# Power.net
KiCad netlist of a schematic drawn in Altium Designer
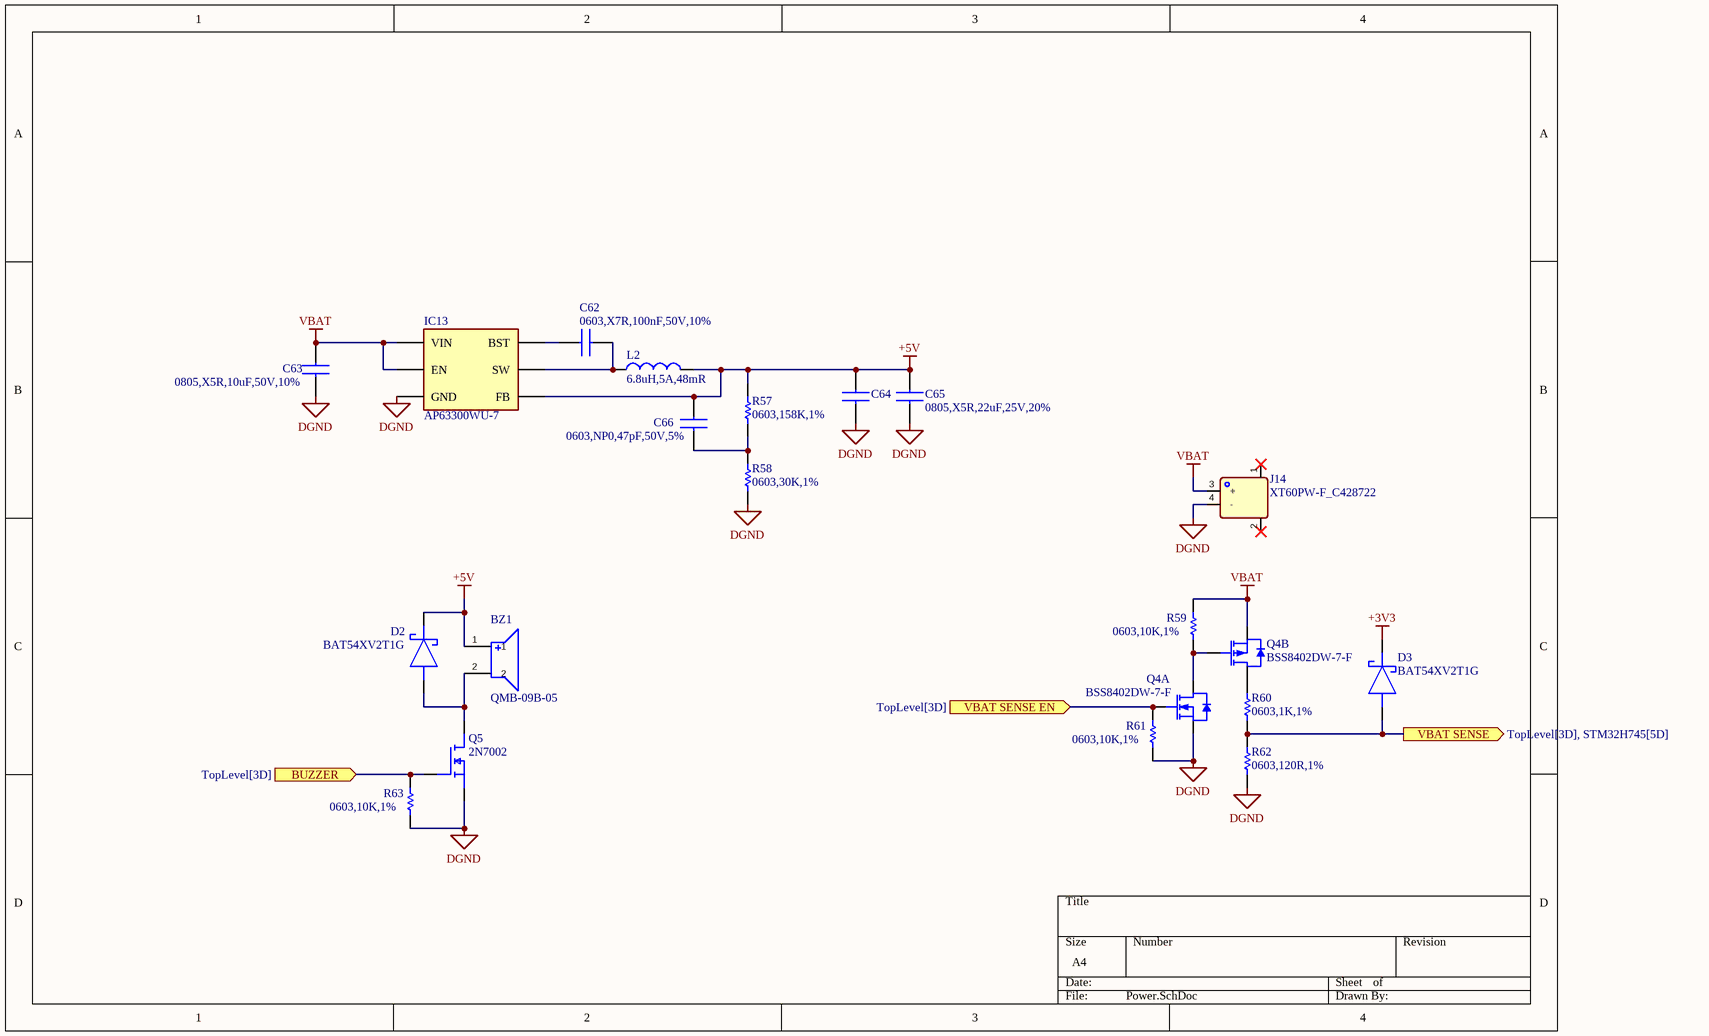
[diagram p0: Power.SchDoc]

(export (version "E")
  (design (tool "Eeschema 10.0.6"))
  (components
    (comp (ref "BZ1")
      (value "QMB-09B-05")
      (footprint "QMB-09B-05")
      (fields (field (name "LCSC PART #") "C161819"))
      (libsource (lib "flight-controller") (part "QMB-09B-05"))
    )
    (comp (ref "C62")
      (value "0603,X7R,100nF,50V,10%")
      (footprint "CAPC1608X90N")
      (description "50V 100nF X7R ±10% 0603 Multilayer Ceramic Capacitors MLCC - SMD/SMT ROHS")
      (fields (field (name "LCSC PART #") "C14663") (field (name "MANU PART #") "CC0603KRX7R9BB104"))
      (libsource (lib "flight-controller") (part "CC0603KRX7R9BB104"))
    )
    (comp (ref "C63")
      (value "0805,X5R,10uF,50V,10%")
      (footprint "CAPC2012X145N")
      (description "10uF 50V X5R ±10% 0805 Multilayer Ceramic Capacitors MLCC - SMD/SMT ROHS")
      (fields (field (name "LCSC PART #") "C440198") (field (name "MANU PART #") "GRM21BR61H106KE43L"))
      (libsource (lib "flight-controller") (part "GRM21BR61H106KE43L"))
    )
    (comp (ref "C64")
      (value "0805,X5R,22uF,25V,20%")
      (footprint "CAPC2012X145N")
      (description "22uF ±20% 25V Ceramic Capacitor X5R 0805")
      (fields (field (name "LCSC PART #") "C45783") (field (name "MANU PART #") "CL21A226MAQNNNE"))
      (libsource (lib "flight-controller") (part "CL21A226MAQNNNE"))
    )
    (comp (ref "C65")
      (value "0805,X5R,22uF,25V,20%")
      (footprint "CAPC2012X145N")
      (description "22uF ±20% 25V Ceramic Capacitor X5R 0805")
      (fields (field (name "LCSC PART #") "C45783") (field (name "MANU PART #") "CL21A226MAQNNNE"))
      (libsource (lib "flight-controller") (part "CL21A226MAQNNNE"))
    )
    (comp (ref "C66")
      (value "0603,NP0,47pF,50V,5%")
      (footprint "CAPC1608X90N")
      (description "47 pF ±5% 50V Ceramic Capacitor C0G, NP0 0603 (1608 Metric)")
      (fields (field (name "MANU PART #") "CL10C470JB8NNNC") (field (name "LCSC PART #") "C1671"))
      (libsource (lib "flight-controller") (part "CL10C470JB8NNNC"))
    )
    (comp (ref "D2")
      (value "BAT54XV2T1G")
      (footprint "SOD523")
      (description "Diode 30V 200mA Surface Mount SOD-523")
      (fields (field (name "LCSC PART #") "C81572"))
      (libsource (lib "flight-controller") (part "BAT54XV2T1G"))
    )
    (comp (ref "D3")
      (value "BAT54XV2T1G")
      (footprint "SOD523")
      (description "Diode 30V 200mA Surface Mount SOD-523")
      (fields (field (name "LCSC PART #") "C81572"))
      (libsource (lib "flight-controller") (part "BAT54XV2T1G"))
    )
    (comp (ref "IC13")
      (value "AP63300WU-7")
      (footprint "SOT95P280X90-6N")
      (description "3.8V to 32V Input, 3A Low IQ Synchronous Buck Converter with Enhanced EMI Reduction")
      (fields (field (name "LCSC PART #") "C2158012"))
      (libsource (lib "flight-controller") (part "AP63300WU-7"))
    )
    (comp (ref "J14")
      (value "XT60PW-F_C428722")
      (footprint "XT60PW-F_C428722")
      (description "Horizontal plug Yellow - Power connector / plug connector")
      (fields (field (name "LCSC PART #") "C428722") (field (name "MANU PART #") "XT60PW-F"))
      (libsource (lib "flight-controller") (part "XT60PW-F_C428722"))
    )
    (comp (ref "L2")
      (value "6.8uH,5A,48mR")
      (footprint "FXL0630-6R8-M")
      (description "48mΩ 5A 6.8uH 6A Molded Inductor ±20% SMD,7x6.6mm Power Inductors ROHS")
      (fields (field (name "MANU PART #") "FXL0630-6R8-M") (field (name "LCSC PART #") "C167221"))
      (libsource (lib "flight-controller") (part "FXL0630-6R8-M"))
    )
    (comp (ref "Q4")
      (value "BSS8402DW-7-F")
      (footprint "SOT65P210X110-6N")
      (description "N-Channel+P-Channel Array 60V 130mA 200mW Surface Mount SOT-363")
      (fields (field (name "LCSC PART #") "C156386"))
      (libsource (lib "flight-controller") (part "BSS8402DW-7-F"))
    )
    (comp (ref "Q5")
      (value "2N7002")
      (footprint "SOT95P230X110-3N")
      (description "N-Channel 60V 300mA 830mW Surface Mount SOT-23")
      (fields (field (name "LCSC PART #") "C8545"))
      (libsource (lib "flight-controller") (part "2N7002"))
    )
    (comp (ref "R57")
      (value "0603,158K,1%")
      (footprint "RESC1608X90N")
      (fields (field (name "MANU PART #") "0603WAF1583T5E") (field (name "LCSC PART #") "C22883"))
      (libsource (lib "flight-controller") (part "0603WAF1583T5E"))
    )
    (comp (ref "R58")
      (value "0603,30K,1%")
      (footprint "RESC1608X90N")
      (fields (field (name "LCSC PART #") "C22984") (field (name "MANU PART #") "0603WAF3002T5E"))
      (libsource (lib "flight-controller") (part "0603WAF3002T5E"))
    )
    (comp (ref "R59")
      (value "0603,10K,1%")
      (footprint "RESC1608X90N")
      (description "100mW Thick Film Resistor 75V ±100ppm/℃ ±1% 10kΩ 0603 Chip Resistor - Surface Mount ROHS")
      (fields (field (name "LCSC PART #") "C25804") (field (name "MANU PART #") "0603WAF1002T5E"))
      (libsource (lib "flight-controller") (part "0603WAF1002T5E"))
    )
    (comp (ref "R60")
      (value "0603,1K,1%")
      (footprint "RESC1608X90N")
      (description "100mW 1kΩ 75V Thick Film Resistor ±100ppm/℃ ±1% 0603 Chip Resistor - Surface Mount RoHS")
      (fields (field (name "LCSC PART #") "C21190") (field (name "MANU PART #") "0603WAF1001T5E"))
      (libsource (lib "flight-controller") (part "0603WAF1001T5E"))
    )
    (comp (ref "R61")
      (value "0603,10K,1%")
      (footprint "RESC1608X90N")
      (description "100mW Thick Film Resistor 75V ±100ppm/℃ ±1% 10kΩ 0603 Chip Resistor - Surface Mount ROHS")
      (fields (field (name "LCSC PART #") "C25804") (field (name "MANU PART #") "0603WAF1002T5E"))
      (libsource (lib "flight-controller") (part "0603WAF1002T5E"))
    )
    (comp (ref "R62")
      (value "0603,120R,1%")
      (footprint "RESC1608X90N")
      (fields (field (name "MANU PART #") "0603WAF1200T5E") (field (name "LCSC PART #") "C22787"))
      (libsource (lib "flight-controller") (part "0603WAF1200T5E"))
    )
    (comp (ref "R63")
      (value "0603,10K,1%")
      (footprint "RESC1608X90N")
      (description "100mW Thick Film Resistor 75V ±100ppm/℃ ±1% 10kΩ 0603 Chip Resistor - Surface Mount ROHS")
      (fields (field (name "LCSC PART #") "C25804") (field (name "MANU PART #") "0603WAF1002T5E"))
      (libsource (lib "flight-controller") (part "0603WAF1002T5E"))
    )
  )
  (nets
    (net (code "1") (name "+3V3") (class "Default")
      (node (ref "D3") (pin "1") (pinfunction "K_1") (pintype "passive"))
    )
    (net (code "2") (name "+5V") (class "Default")
      (node (ref "BZ1") (pin "1") (pinfunction "1_1") (pintype "passive"))
      (node (ref "C64") (pin "2") (pinfunction "2_2") (pintype "passive"))
      (node (ref "C65") (pin "2") (pinfunction "2_2") (pintype "passive"))
      (node (ref "C66") (pin "2") (pinfunction "2_2") (pintype "passive"))
      (node (ref "D2") (pin "1") (pinfunction "K_1") (pintype "passive"))
      (node (ref "IC13") (pin "1") (pinfunction "FB_1") (pintype "passive"))
      (node (ref "L2") (pin "2") (pinfunction "2_2") (pintype "passive"))
      (node (ref "R57") (pin "2") (pinfunction "2_2") (pintype "passive"))
    )
    (net (code "3") (name "/BUZZER") (class "Default")
      (node (ref "Q5") (pin "1") (pinfunction "G_1") (pintype "passive"))
      (node (ref "R63") (pin "2") (pinfunction "2_2") (pintype "passive"))
    )
    (net (code "4") (name "/VBAT SENSE") (class "Default")
      (node (ref "D3") (pin "2") (pinfunction "A_2") (pintype "passive"))
      (node (ref "R60") (pin "1") (pinfunction "1_1") (pintype "passive"))
      (node (ref "R62") (pin "2") (pinfunction "2_2") (pintype "passive"))
    )
    (net (code "5") (name "/VBAT SENSE EN") (class "Default")
      (node (ref "Q4") (pin "2") (pinfunction "G1_2") (pintype "passive"))
      (node (ref "R61") (pin "2") (pinfunction "2_2") (pintype "passive"))
    )
    (net (code "6") (name "DGND") (class "Default")
      (node (ref "C63") (pin "1") (pinfunction "1_1") (pintype "passive"))
      (node (ref "C64") (pin "1") (pinfunction "1_1") (pintype "passive"))
      (node (ref "C65") (pin "1") (pinfunction "1_1") (pintype "passive"))
      (node (ref "IC13") (pin "4") (pinfunction "GND_4") (pintype "passive"))
      (node (ref "J14") (pin "4") (pinfunction "-_4") (pintype "passive"))
      (node (ref "Q4") (pin "1") (pinfunction "S1_1") (pintype "passive"))
      (node (ref "Q5") (pin "2") (pinfunction "S_2") (pintype "passive"))
      (node (ref "R58") (pin "1") (pinfunction "1_1") (pintype "passive"))
      (node (ref "R61") (pin "1") (pinfunction "1_1") (pintype "passive"))
      (node (ref "R62") (pin "1") (pinfunction "1_1") (pintype "passive"))
      (node (ref "R63") (pin "1") (pinfunction "1_1") (pintype "passive"))
    )
    (net (code "7") (name "Net-(C66-Pad1)") (class "Default")
      (node (ref "C66") (pin "1") (pinfunction "1_1") (pintype "passive"))
      (node (ref "R57") (pin "1") (pinfunction "1_1") (pintype "passive"))
      (node (ref "R58") (pin "2") (pinfunction "2_2") (pintype "passive"))
    )
    (net (code "8") (name "Net-(D2-A)") (class "Default")
      (node (ref "BZ1") (pin "2") (pinfunction "2_2") (pintype "passive"))
      (node (ref "D2") (pin "2") (pinfunction "A_2") (pintype "passive"))
      (node (ref "Q5") (pin "3") (pinfunction "D_3") (pintype "passive"))
    )
    (net (code "9") (name "Net-(IC13-BST)") (class "Default")
      (node (ref "C62") (pin "1") (pinfunction "1_1") (pintype "passive"))
      (node (ref "IC13") (pin "6") (pinfunction "BST_6") (pintype "passive"))
    )
    (net (code "10") (name "Net-(IC13-SW)") (class "Default")
      (node (ref "C62") (pin "2") (pinfunction "2_2") (pintype "passive"))
      (node (ref "IC13") (pin "5") (pinfunction "SW_5") (pintype "passive"))
      (node (ref "L2") (pin "1") (pinfunction "1_1") (pintype "passive"))
    )
    (net (code "11") (name "Net-(Q4A-D1)") (class "Default")
      (node (ref "Q4") (pin "5") (pinfunction "G2_5") (pintype "passive"))
      (node (ref "Q4") (pin "6") (pinfunction "D1_6") (pintype "passive"))
      (node (ref "R59") (pin "1") (pinfunction "1_1") (pintype "passive"))
    )
    (net (code "12") (name "Net-(Q4B-D2)") (class "Default")
      (node (ref "Q4") (pin "3") (pinfunction "D2_3") (pintype "passive"))
      (node (ref "R60") (pin "2") (pinfunction "2_2") (pintype "passive"))
    )
    (net (code "13") (name "VBAT") (class "Default")
      (node (ref "C63") (pin "2") (pinfunction "2_2") (pintype "passive"))
      (node (ref "IC13") (pin "2") (pinfunction "EN_2") (pintype "passive"))
      (node (ref "IC13") (pin "3") (pinfunction "VIN_3") (pintype "passive"))
      (node (ref "J14") (pin "3") (pinfunction "+_3") (pintype "passive"))
      (node (ref "Q4") (pin "4") (pinfunction "S2_4") (pintype "passive"))
      (node (ref "R59") (pin "2") (pinfunction "2_2") (pintype "passive"))
    )
    (net (code "14") (name "unconnected-(J14-Pad1)") (class "Default")
      (node (ref "J14") (pin "1") (pinfunction "1_1") (pintype "passive+no_connect"))
    )
    (net (code "15") (name "unconnected-(J14-Pad2)") (class "Default")
      (node (ref "J14") (pin "2") (pinfunction "2_2") (pintype "passive+no_connect"))
    )
  )
)
